# power_conversion.net
KiCad netlist of a schematic drawn in Altium Designer
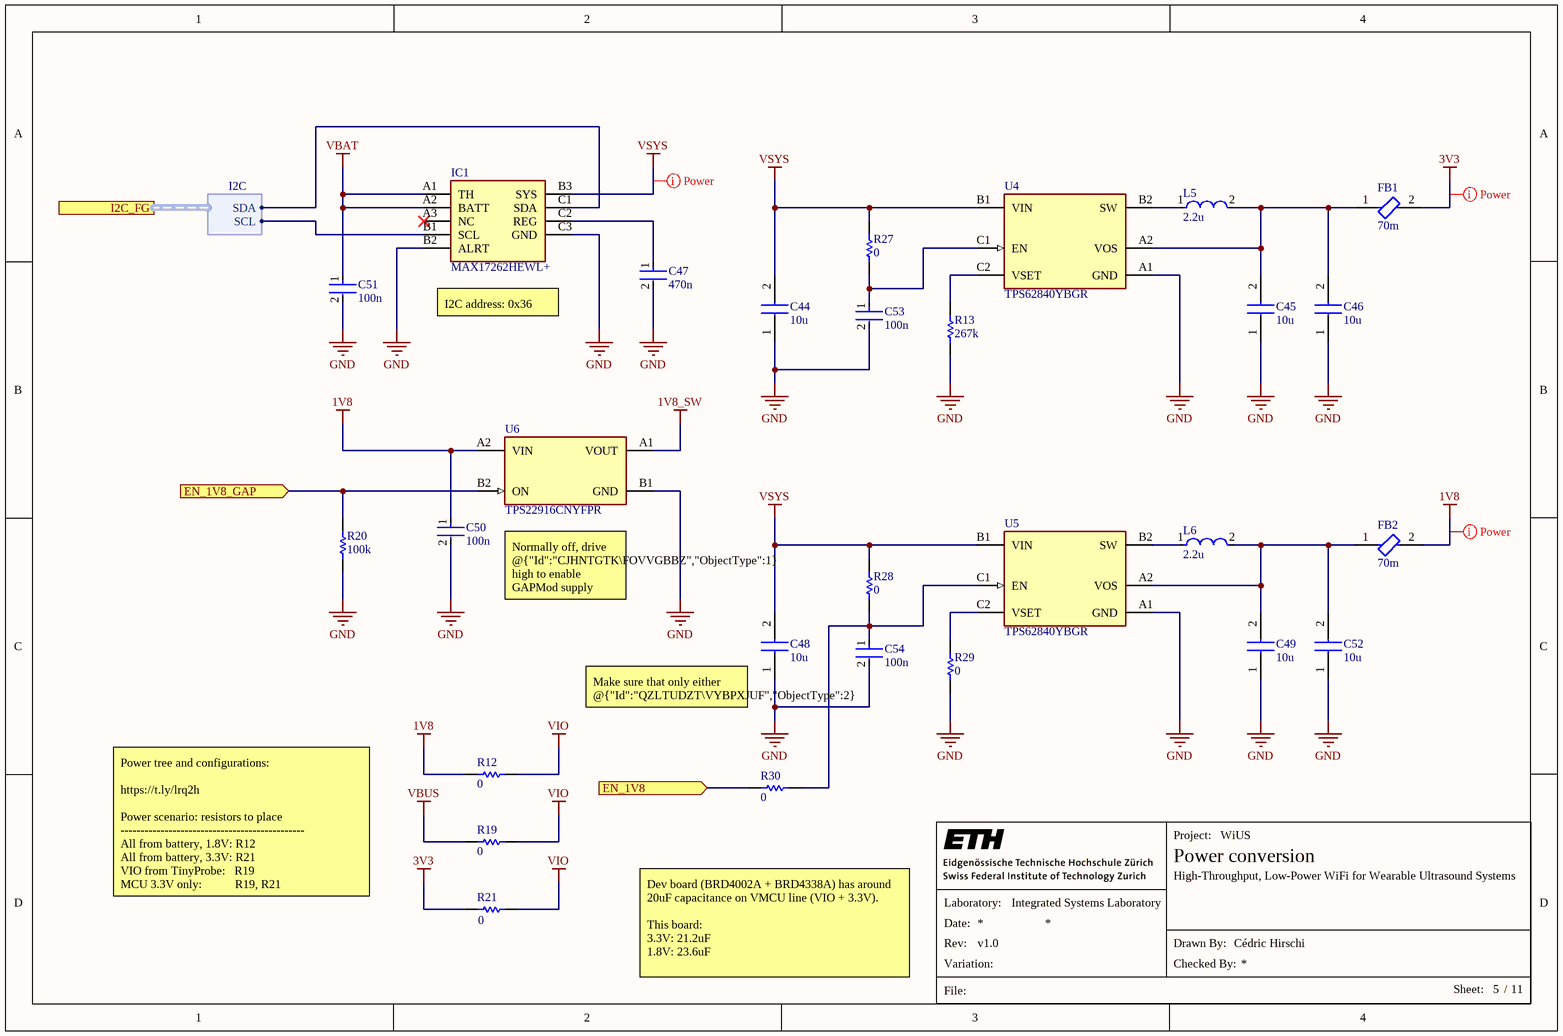
[diagram p0: power_conversion.SchDoc]

(export (version "E")
  (design (tool "Eeschema 10.0.6"))
  (components
    (comp (ref "C44")
      (value "10u")
      (footprint "SamacSys:CAPC1608X100N")
      (description "Cap Cer 10UF 10V X7R 0603")
      (fields (field (name "MANUFACTURER_PART_NUMBER") "GMC10X7R106K10NT"))
      (libsource (lib "*") (part "GMC10X7R106K10NT"))
    )
    (comp (ref "C45")
      (value "10u")
      (footprint "SamacSys:CAPC1608X100N")
      (description "Cap Cer 10UF 10V X7R 0603")
      (fields (field (name "MANUFACTURER_PART_NUMBER") "GMC10X7R106K10NT"))
      (libsource (lib "*") (part "GMC10X7R106K10NT"))
    )
    (comp (ref "C46")
      (value "10u")
      (footprint "SamacSys:CAPC1608X100N")
      (description "Cap Cer 10UF 10V X7R 0603")
      (fields (field (name "MANUFACTURER_PART_NUMBER") "GMC10X7R106K10NT"))
      (libsource (lib "*") (part "GMC10X7R106K10NT"))
    )
    (comp (ref "C47")
      (value "470n")
      (footprint "FP-GRM15-0_1-MFG")
      (description "CAP CER 0.47UF 10V X5R 0402")
      (fields
        (field (name "MANUFACTURER") "Murata Electronics North America")
        (field (name "MANUFACTURER PART NUMBER") "GRM155R61A474KE15D")
      )
      (libsource (lib "Altium Content Vault") (part "11868f565c42a9108669ba33697ecf6"))
    )
    (comp (ref "C48")
      (value "10u")
      (footprint "SamacSys:CAPC1608X100N")
      (description "Cap Cer 10UF 10V X7R 0603")
      (fields (field (name "MANUFACTURER_PART_NUMBER") "GMC10X7R106K10NT"))
      (libsource (lib "*") (part "GMC10X7R106K10NT"))
    )
    (comp (ref "C49")
      (value "10u")
      (footprint "SamacSys:CAPC1608X100N")
      (description "Cap Cer 10UF 10V X7R 0603")
      (fields (field (name "MANUFACTURER_PART_NUMBER") "GMC10X7R106K10NT"))
      (libsource (lib "*") (part "GMC10X7R106K10NT"))
    )
    (comp (ref "C50")
      (value "100n")
      (footprint "FP-GRT155-0_05-MFG")
      (description "Multi-Layer Ceramic Capacitor 100nF 50V X7R ±10% 0402 Paper T/R")
      (libsource (lib "Altium Content Vault") (part "02cd4be3c70576c341d710602a673aa"))
    )
    (comp (ref "C51")
      (value "100n")
      (footprint "FP-GRT155-0_05-MFG")
      (description "Multi-Layer Ceramic Capacitor 100nF 50V X7R ±10% 0402 Paper T/R")
      (libsource (lib "Altium Content Vault") (part "02cd4be3c70576c341d710602a673aa"))
    )
    (comp (ref "C52")
      (value "10u")
      (footprint "SamacSys:CAPC1608X100N")
      (description "Cap Cer 10UF 10V X7R 0603")
      (fields (field (name "MANUFACTURER_PART_NUMBER") "GMC10X7R106K10NT"))
      (libsource (lib "*") (part "GMC10X7R106K10NT"))
    )
    (comp (ref "C53")
      (value "100n")
      (footprint "FP-GRT155-0_05-MFG")
      (description "Multi-Layer Ceramic Capacitor 100nF 50V X7R ±10% 0402 Paper T/R")
      (libsource (lib "Altium Content Vault") (part "02cd4be3c70576c341d710602a673aa"))
    )
    (comp (ref "C54")
      (value "100n")
      (footprint "FP-GRT155-0_05-MFG")
      (description "Multi-Layer Ceramic Capacitor 100nF 50V X7R ±10% 0402 Paper T/R")
      (libsource (lib "Altium Content Vault") (part "02cd4be3c70576c341d710602a673aa"))
    )
    (comp (ref "FB1")
      (value "70m")
      (footprint "FP-BLM15-0_05-MFG")
      (description "Chip Ferrite Bead, 0402, 80Ω @ 100MHz, 0.07Ω, 25%, 1.5A")
      (fields (field (name "TOLERANCE") "25%"))
      (libsource (lib "Altium Content Vault") (part "5f30dd21d616792df468990f7003faa"))
    )
    (comp (ref "FB2")
      (value "70m")
      (footprint "FP-BLM15-0_05-MFG")
      (description "Chip Ferrite Bead, 0402, 80Ω @ 100MHz, 0.07Ω, 25%, 1.5A")
      (fields (field (name "TOLERANCE") "25%"))
      (libsource (lib "Altium Content Vault") (part "5f30dd21d616792df468990f7003faa"))
    )
    (comp (ref "IC1")
      (value "MAX17262HEWL+")
      (footprint "SamacSys:BGA9C40P3X3_153X153X69")
      (description "Integrated Circuit")
      (libsource (lib "*") (part "MAX17262HEWL+"))
    )
    (comp (ref "L5")
      (value "2.2u")
      (footprint "FP-DFE201612C-MFG")
      (description "Shielded Wirewound Inductor 2.2uH 20% 1800mA 0.116Ω 0806 (2016)")
      (libsource (lib "Altium Content Vault") (part "725321dda6339637d4d059423bc1c3c"))
    )
    (comp (ref "L6")
      (value "2.2u")
      (footprint "FP-DFE201612C-MFG")
      (description "Shielded Wirewound Inductor 2.2uH 20% 1800mA 0.116Ω 0806 (2016)")
      (libsource (lib "Altium Content Vault") (part "725321dda6339637d4d059423bc1c3c"))
    )
    (comp (ref "R12")
      (value "0")
      (footprint "RESC1005X40X25ML05T10")
      (description "Chip Resistor, 0 Ohm, 0.063 W, -55 to 155 degC, 0402 (1005 Metric)")
      (fields (field (name "POWER") "63mW") (field (name "Comment") "Resistor 0R 0402 63 mW"))
      (libsource (lib "Cédric's Workspace") (part "RES-2"))
    )
    (comp (ref "R13")
      (value "267k")
      (footprint "RESC1005X40X25LL05T10")
      (fields (field (name "MANUFACTURER") "Yageo") (field (name "PART NUMBER") "RC0402FR-07267KL"))
      (libsource (lib "Altium Content Vault") (part "RES"))
    )
    (comp (ref "R19")
      (value "0")
      (footprint "RESC1005X40X25ML05T10")
      (description "Chip Resistor, 0 Ohm, 0.063 W, -55 to 155 degC, 0402 (1005 Metric)")
      (fields (field (name "POWER") "63mW") (field (name "Comment") "Resistor 0R 0402 63 mW"))
      (libsource (lib "Cédric's Workspace") (part "RES-2"))
    )
    (comp (ref "R20")
      (value "100k")
      (footprint "RESC1005X40X25NL05T10")
      (fields (field (name "PART NUMBER") "RC0402FR-07100KL") (field (name "MANUFACTURER") "Yageo / Phycomp"))
      (libsource (lib "Altium Content Vault") (part "RES"))
    )
    (comp (ref "R21")
      (value "0")
      (footprint "RESC1005X40X25ML05T10")
      (description "Chip Resistor, 0 Ohm, 0.063 W, -55 to 155 degC, 0402 (1005 Metric)")
      (fields (field (name "POWER") "63mW") (field (name "Comment") "Resistor 0R 0402 63 mW"))
      (libsource (lib "Cédric's Workspace") (part "RES-2"))
    )
    (comp (ref "R27")
      (value "0")
      (footprint "RESC1005X40X25ML05T10")
      (description "Chip Resistor, 0 Ohm, 0.063 W, -55 to 155 degC, 0402 (1005 Metric)")
      (fields (field (name "POWER") "63mW") (field (name "Comment") "Resistor 0R 0402 63 mW"))
      (libsource (lib "Cédric's Workspace") (part "RES-2"))
    )
    (comp (ref "R28")
      (value "0")
      (footprint "RESC1005X40X25ML05T10")
      (description "Chip Resistor, 0 Ohm, 0.063 W, -55 to 155 degC, 0402 (1005 Metric)")
      (fields (field (name "POWER") "63mW") (field (name "Comment") "Resistor 0R 0402 63 mW"))
      (libsource (lib "Cédric's Workspace") (part "RES-2"))
    )
    (comp (ref "R29")
      (value "0")
      (footprint "RESC1005X40X25ML05T10")
      (description "Chip Resistor, 0 Ohm, 0.063 W, -55 to 155 degC, 0402 (1005 Metric)")
      (fields (field (name "POWER") "63mW") (field (name "Comment") "Resistor 0R 0402 63 mW"))
      (libsource (lib "Cédric's Workspace") (part "RES-2"))
    )
    (comp (ref "R30")
      (value "0")
      (footprint "RESC1005X40X25ML05T10")
      (description "Chip Resistor, 0 Ohm, 0.063 W, -55 to 155 degC, 0402 (1005 Metric)")
      (fields (field (name "POWER") "63mW") (field (name "Comment") "Resistor 0R 0402 63 mW"))
      (libsource (lib "Cédric's Workspace") (part "RES-2"))
    )
    (comp (ref "U4")
      (value "TPS62840YBGR")
      (footprint "FP-YBG0006-MFG")
      (description "ULTRA LOW IQ BUCK CONVERTER")
      (libsource (lib "Altium Content Vault") (part "c4b2ba52c5c06523be8e235897d707d"))
    )
    (comp (ref "U5")
      (value "TPS62840YBGR")
      (footprint "FP-YBG0006-MFG")
      (description "ULTRA LOW IQ BUCK CONVERTER")
      (libsource (lib "Altium Content Vault") (part "c4b2ba52c5c06523be8e235897d707d"))
    )
    (comp (ref "U6")
      (value "TPS22916CNYFPR")
      (footprint "FP-YFP0004-IPC_C")
      (description "IC PWR SWITCH P-CHAN 1:1 4DSBGA")
      (libsource (lib "Altium Content Vault") (part "1899b175ee913ee136282ba2e26d23c"))
    )
  )
  (nets
    (net (code "2") (name "/EN_1V8") (class "Default")
      (node (ref "R30") (pin "1") (pinfunction "1_1") (pintype "passive"))
    )
    (net (code "3") (name "/EN_1V8_GAP") (class "Default")
      (node (ref "R20") (pin "2") (pinfunction "2_2") (pintype "passive"))
      (node (ref "U6") (pin "B2") (pinfunction "ON_B2") (pintype "input"))
    )
    (net (code "4") (name "/SCL") (class "Default")
      (node (ref "IC1") (pin "B1") (pinfunction "SCL_B1") (pintype "passive"))
    )
    (net (code "5") (name "/SDA") (class "Default")
      (node (ref "IC1") (pin "C1") (pinfunction "SDA_C1") (pintype "passive"))
    )
    (net (code "7") (name "1V8") (class "Default")
      (node (ref "C50") (pin "1") (pinfunction "1_1") (pintype "passive"))
      (node (ref "FB2") (pin "2") (pinfunction "2_2") (pintype "passive"))
      (node (ref "R12") (pin "2") (pinfunction "2_2") (pintype "passive"))
      (node (ref "U6") (pin "A2") (pinfunction "VIN_A2") (pintype "power_in"))
    )
    (net (code "8") (name "1V8_SW") (class "Default")
      (node (ref "U6") (pin "A1") (pinfunction "VOUT_A1") (pintype "power_in"))
    )
    (net (code "9") (name "3V3") (class "Default")
      (node (ref "FB1") (pin "2") (pinfunction "2_2") (pintype "passive"))
      (node (ref "R21") (pin "1") (pinfunction "1_1") (pintype "passive"))
    )
    (net (code "10") (name "GND") (class "Default")
      (node (ref "C44") (pin "1") (pinfunction "1_1") (pintype "passive"))
      (node (ref "C45") (pin "1") (pinfunction "1_1") (pintype "passive"))
      (node (ref "C46") (pin "1") (pinfunction "1_1") (pintype "passive"))
      (node (ref "C47") (pin "2") (pinfunction "2_2") (pintype "passive"))
      (node (ref "C48") (pin "1") (pinfunction "1_1") (pintype "passive"))
      (node (ref "C49") (pin "1") (pinfunction "1_1") (pintype "passive"))
      (node (ref "C50") (pin "2") (pinfunction "2_2") (pintype "passive"))
      (node (ref "C51") (pin "2") (pinfunction "2_2") (pintype "passive"))
      (node (ref "C52") (pin "1") (pinfunction "1_1") (pintype "passive"))
      (node (ref "C53") (pin "2") (pinfunction "2_2") (pintype "passive"))
      (node (ref "C54") (pin "2") (pinfunction "2_2") (pintype "passive"))
      (node (ref "IC1") (pin "B2") (pinfunction "ALRT_B2") (pintype "passive"))
      (node (ref "IC1") (pin "C3") (pinfunction "GND_C3") (pintype "passive"))
      (node (ref "R13") (pin "1") (pinfunction "1_1") (pintype "passive"))
      (node (ref "R20") (pin "1") (pinfunction "1_1") (pintype "passive"))
      (node (ref "R29") (pin "2") (pinfunction "2_2") (pintype "passive"))
      (node (ref "U4") (pin "A1") (pinfunction "GND_A1") (pintype "power_in"))
      (node (ref "U5") (pin "A1") (pinfunction "GND_A1") (pintype "power_in"))
      (node (ref "U6") (pin "B1") (pinfunction "GND_B1") (pintype "power_in"))
    )
    (net (code "11") (name "Net-(IC1-REG)") (class "Default")
      (node (ref "C47") (pin "1") (pinfunction "1_1") (pintype "passive"))
      (node (ref "IC1") (pin "C2") (pinfunction "REG_C2") (pintype "passive"))
    )
    (net (code "12") (name "Net-(U4-EN)") (class "Default")
      (node (ref "C53") (pin "1") (pinfunction "1_1") (pintype "passive"))
      (node (ref "R27") (pin "2") (pinfunction "2_2") (pintype "passive"))
      (node (ref "U4") (pin "C1") (pinfunction "EN_C1") (pintype "input"))
    )
    (net (code "13") (name "Net-(U4-SW)") (class "Default")
      (node (ref "L5") (pin "1") (pinfunction "1_1") (pintype "passive"))
      (node (ref "U4") (pin "B2") (pinfunction "SW_B2") (pintype "power_in"))
    )
    (net (code "14") (name "Net-(U4-VOS)") (class "Default")
      (node (ref "C45") (pin "2") (pinfunction "2_2") (pintype "passive"))
      (node (ref "C46") (pin "2") (pinfunction "2_2") (pintype "passive"))
      (node (ref "FB1") (pin "1") (pinfunction "1_1") (pintype "passive"))
      (node (ref "L5") (pin "2") (pinfunction "2_2") (pintype "passive"))
      (node (ref "U4") (pin "A2") (pinfunction "VOS_A2") (pintype "power_in"))
    )
    (net (code "15") (name "Net-(U4-VSET)") (class "Default")
      (node (ref "R13") (pin "2") (pinfunction "2_2") (pintype "passive"))
      (node (ref "U4") (pin "C2") (pinfunction "VSET_C2") (pintype "power_in"))
    )
    (net (code "16") (name "Net-(U5-EN)") (class "Default")
      (node (ref "C54") (pin "1") (pinfunction "1_1") (pintype "passive"))
      (node (ref "R28") (pin "2") (pinfunction "2_2") (pintype "passive"))
      (node (ref "R30") (pin "2") (pinfunction "2_2") (pintype "passive"))
      (node (ref "U5") (pin "C1") (pinfunction "EN_C1") (pintype "input"))
    )
    (net (code "17") (name "Net-(U5-SW)") (class "Default")
      (node (ref "L6") (pin "1") (pinfunction "1_1") (pintype "passive"))
      (node (ref "U5") (pin "B2") (pinfunction "SW_B2") (pintype "power_in"))
    )
    (net (code "18") (name "Net-(U5-VOS)") (class "Default")
      (node (ref "C49") (pin "2") (pinfunction "2_2") (pintype "passive"))
      (node (ref "C52") (pin "2") (pinfunction "2_2") (pintype "passive"))
      (node (ref "FB2") (pin "1") (pinfunction "1_1") (pintype "passive"))
      (node (ref "L6") (pin "2") (pinfunction "2_2") (pintype "passive"))
      (node (ref "U5") (pin "A2") (pinfunction "VOS_A2") (pintype "power_in"))
    )
    (net (code "19") (name "Net-(U5-VSET)") (class "Default")
      (node (ref "R29") (pin "1") (pinfunction "1_1") (pintype "passive"))
      (node (ref "U5") (pin "C2") (pinfunction "VSET_C2") (pintype "power_in"))
    )
    (net (code "20") (name "VBAT") (class "Default")
      (node (ref "C51") (pin "1") (pinfunction "1_1") (pintype "passive"))
      (node (ref "IC1") (pin "A1") (pinfunction "TH_A1") (pintype "passive"))
      (node (ref "IC1") (pin "A2") (pinfunction "BATT_A2") (pintype "passive"))
    )
    (net (code "21") (name "VBUS") (class "Default")
      (node (ref "R19") (pin "2") (pinfunction "2_2") (pintype "passive"))
    )
    (net (code "22") (name "VIO") (class "Default")
      (node (ref "R12") (pin "1") (pinfunction "1_1") (pintype "passive"))
      (node (ref "R19") (pin "1") (pinfunction "1_1") (pintype "passive"))
      (node (ref "R21") (pin "2") (pinfunction "2_2") (pintype "passive"))
    )
    (net (code "23") (name "VSYS") (class "Default")
      (node (ref "C44") (pin "2") (pinfunction "2_2") (pintype "passive"))
      (node (ref "C48") (pin "2") (pinfunction "2_2") (pintype "passive"))
      (node (ref "IC1") (pin "B3") (pinfunction "SYS_B3") (pintype "passive"))
      (node (ref "R27") (pin "1") (pinfunction "1_1") (pintype "passive"))
      (node (ref "R28") (pin "1") (pinfunction "1_1") (pintype "passive"))
      (node (ref "U4") (pin "B1") (pinfunction "VIN_B1") (pintype "power_in"))
      (node (ref "U5") (pin "B1") (pinfunction "VIN_B1") (pintype "power_in"))
    )
    (net (code "24") (name "unconnected-(IC1-NC-PadA3)") (class "Default")
      (node (ref "IC1") (pin "A3") (pinfunction "NC_A3") (pintype "passive+no_connect"))
    )
  )
)
